# I2C-SPI_Communication.net
KiCad netlist of a schematic drawn in Altium Designer
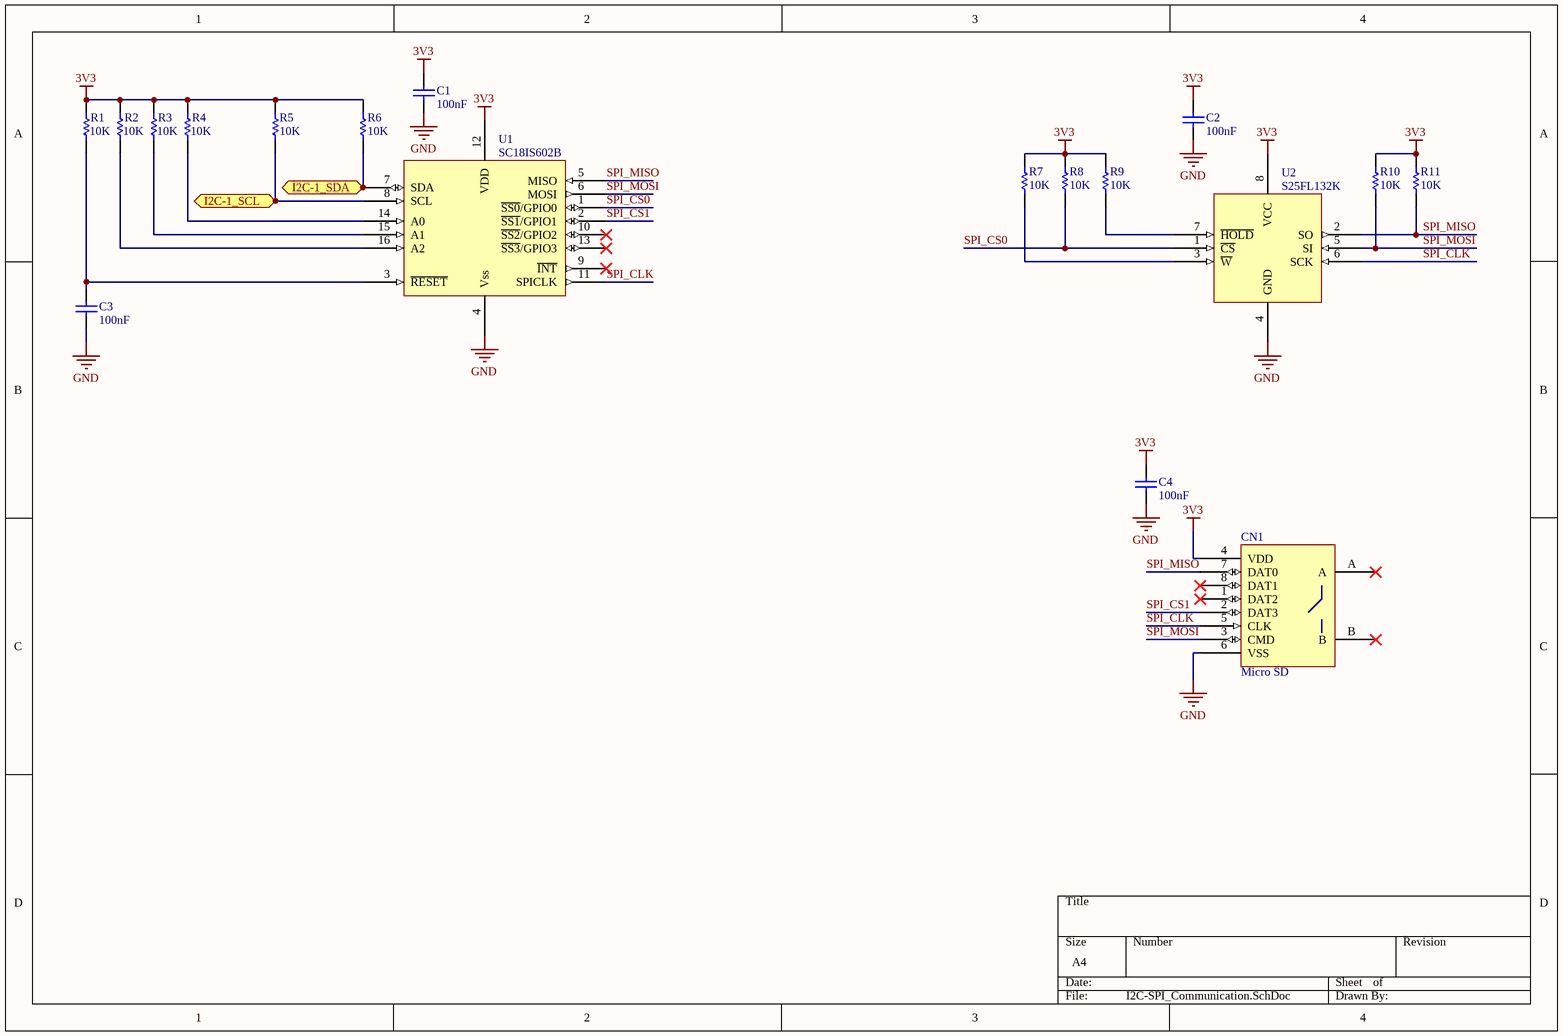
[diagram p0: I2C-SPI_Communication.SchDoc]

(export (version "E")
  (design (tool "Eeschema 10.0.6"))
  (components
    (comp (ref "C1")
      (value "100nF")
      (footprint "OBC_pcblib:CC1005-0402")
      (description "CAP CER 0.1UF 16V 10% X7R 0402")
      (fields
        (field (name "EVENDOR PART#") "490-3261-1-ND")
        (field (name "MANUFACTURER") "Murata Electronics North America")
      )
      (libsource (lib "OBC_schlib") (part "Capacitor"))
    )
    (comp (ref "C2")
      (value "100nF")
      (footprint "OBC_pcblib:CC1005-0402")
      (description "CAP CER 0.1UF 16V 10% X7R 0402")
      (fields
        (field (name "EVENDOR PART#") "490-3261-1-ND")
        (field (name "MANUFACTURER") "Murata Electronics North America")
      )
      (libsource (lib "OBC_schlib") (part "Capacitor"))
    )
    (comp (ref "C3")
      (value "100nF")
      (footprint "OBC_pcblib:CC1005-0402")
      (description "Capacitor")
      (libsource (lib "Schlib1") (part "Capacitor"))
    )
    (comp (ref "C4")
      (value "100nF")
      (footprint "OBC_pcblib:CC1005-0402")
      (description "CAP CER 0.1UF 16V 10% X7R 0402")
      (fields
        (field (name "EVENDOR PART#") "490-3261-1-ND")
        (field (name "MANUFACTURER") "Murata Electronics North America")
      )
      (libsource (lib "OBC_schlib") (part "Capacitor"))
    )
    (comp (ref "CN1")
      (value "Micro SD")
      (footprint "OBC_pcblib:MICROSD")
      (description "CONN MICRO SD R/A PUSH-PULL SMD")
      (fields
        (field (name "EVENDOR PART#") "HR1941CT-ND")
        (field (name "MANUFACTURER") "Hirose Electric Co Ltd")
      )
      (libsource (lib "Schlib1") (part "Micro SD"))
    )
    (comp (ref "R1")
      (value "10K")
      (footprint "AXIAL-0.3")
      (description "Resistor")
      (fields (field (name "Comment") "Res1") (field (name "PUBLISHER") "Altium Limited"))
      (libsource (lib "Miscellaneous Devices") (part "Res1"))
    )
    (comp (ref "R2")
      (value "10K")
      (footprint "AXIAL-0.3")
      (description "Resistor")
      (fields (field (name "Comment") "Res1") (field (name "PUBLISHER") "Altium Limited"))
      (libsource (lib "Miscellaneous Devices") (part "Res1"))
    )
    (comp (ref "R3")
      (value "10K")
      (footprint "AXIAL-0.3")
      (description "Resistor")
      (fields (field (name "Comment") "Res1") (field (name "PUBLISHER") "Altium Limited"))
      (libsource (lib "Miscellaneous Devices") (part "Res1"))
    )
    (comp (ref "R4")
      (value "10K")
      (footprint "AXIAL-0.3")
      (description "Resistor")
      (fields (field (name "Comment") "Res1") (field (name "PUBLISHER") "Altium Limited"))
      (libsource (lib "Miscellaneous Devices") (part "Res1"))
    )
    (comp (ref "R5")
      (value "10K")
      (footprint "OBC_pcblib:CR1005-0402_NP")
      (description "Resistor")
      (libsource (lib "Schlib1") (part "Resistor"))
    )
    (comp (ref "R6")
      (value "10K")
      (footprint "OBC_pcblib:CR1005-0402_NP")
      (description "Resistor")
      (libsource (lib "Schlib1") (part "Resistor"))
    )
    (comp (ref "R7")
      (value "10K")
      (footprint "OBC_pcblib:CR1005-0402")
      (description "RES SMD 10K OHM 1% 1/10W 0402")
      (fields
        (field (name "EVENDOR PART#") "P10.0KLCT-ND")
        (field (name "MANUFACTURER") "Panasonic Electronic Components")
      )
      (libsource (lib "OBC_schlib") (part "Resistor"))
    )
    (comp (ref "R8")
      (value "10K")
      (footprint "OBC_pcblib:CR1005-0402")
      (description "RES SMD 10K OHM 1% 1/10W 0402")
      (fields
        (field (name "EVENDOR PART#") "P10.0KLCT-ND")
        (field (name "MANUFACTURER") "Panasonic Electronic Components")
      )
      (libsource (lib "OBC_schlib") (part "Resistor"))
    )
    (comp (ref "R9")
      (value "10K")
      (footprint "OBC_pcblib:CR1005-0402")
      (description "RES SMD 10K OHM 1% 1/10W 0402")
      (fields
        (field (name "EVENDOR PART#") "P10.0KLCT-ND")
        (field (name "MANUFACTURER") "Panasonic Electronic Components")
      )
      (libsource (lib "OBC_schlib") (part "Resistor"))
    )
    (comp (ref "R10")
      (value "10K")
      (footprint "OBC_pcblib:CR1005-0402")
      (description "RES SMD 10K OHM 1% 1/10W 0402")
      (fields
        (field (name "EVENDOR PART#") "P10.0KLCT-ND")
        (field (name "MANUFACTURER") "Panasonic Electronic Components")
      )
      (libsource (lib "OBC_schlib") (part "Resistor"))
    )
    (comp (ref "R11")
      (value "10K")
      (footprint "OBC_pcblib:CR1005-0402")
      (description "RES SMD 10K OHM 1% 1/10W 0402")
      (fields
        (field (name "EVENDOR PART#") "P10.0KLCT-ND")
        (field (name "MANUFACTURER") "Panasonic Electronic Components")
      )
      (libsource (lib "OBC_schlib") (part "Resistor"))
    )
    (comp (ref "U1")
      (value "SC18IS602B")
      (footprint "TSSOP-16N")
      (description "IC BRIDGE I2C/SPI 16-TSSOP")
      (fields (field (name "EVENDORPART#") "568-10300-1-ND") (field (name "MANUFACTURER") "NXP USA Inc"))
      (libsource (lib "Schlib1") (part "SC18IS602B"))
    )
    (comp (ref "U2")
      (value "S25FL132K")
      (footprint "OBC_pcblib:SOIC-8N")
      (description "Flash 32Mb, 3V, 108Mhz CMOS SPI Flash")
      (fields (field (name "MANUFACTURER") "Spansion") (field (name "EVENDOR PART#") "797-25FL132K0XMFI041"))
      (libsource (lib "OBC_schlib") (part "S25FL132K"))
    )
  )
  (nets
    (net (code "1") (name "/I2C-1_SCL") (class "Default")
      (node (ref "R5") (pin "1") (pinfunction "1_1") (pintype "passive"))
      (node (ref "U1") (pin "8") (pinfunction "SCL_8") (pintype "input"))
    )
    (net (code "2") (name "/I2C-1_SDA") (class "Default")
      (node (ref "R6") (pin "1") (pinfunction "1_1") (pintype "passive"))
      (node (ref "U1") (pin "7") (pinfunction "SDA_7") (pintype "bidirectional"))
    )
    (net (code "3") (name "/SPI_CLK") (class "Default")
      (node (ref "CN1") (pin "5") (pinfunction "CLK_5") (pintype "input"))
      (node (ref "U1") (pin "11") (pinfunction "SPICLK_11") (pintype "output"))
      (node (ref "U2") (pin "6") (pinfunction "SCK_6") (pintype "input"))
    )
    (net (code "4") (name "/SPI_CS0") (class "Default")
      (node (ref "R8") (pin "1") (pinfunction "1_1") (pintype "passive"))
      (node (ref "U1") (pin "1") (pinfunction "~{SS0}/GPIO0_1") (pintype "bidirectional"))
      (node (ref "U2") (pin "1") (pinfunction "~{CS}_1") (pintype "input"))
    )
    (net (code "5") (name "/SPI_CS1") (class "Default")
      (node (ref "CN1") (pin "2") (pinfunction "DAT3_2") (pintype "bidirectional"))
      (node (ref "U1") (pin "2") (pinfunction "~{SS1}/GPIO1_2") (pintype "bidirectional"))
    )
    (net (code "6") (name "/SPI_MISO") (class "Default")
      (node (ref "CN1") (pin "7") (pinfunction "DAT0_7") (pintype "bidirectional"))
      (node (ref "R11") (pin "1") (pinfunction "1_1") (pintype "passive"))
      (node (ref "U1") (pin "5") (pinfunction "MISO_5") (pintype "input"))
      (node (ref "U2") (pin "2") (pinfunction "SO_2") (pintype "output"))
    )
    (net (code "7") (name "/SPI_MOSI") (class "Default")
      (node (ref "CN1") (pin "3") (pinfunction "CMD_3") (pintype "bidirectional"))
      (node (ref "R10") (pin "1") (pinfunction "1_1") (pintype "passive"))
      (node (ref "U1") (pin "6") (pinfunction "MOSI_6") (pintype "output"))
      (node (ref "U2") (pin "5") (pinfunction "SI_5") (pintype "input"))
    )
    (net (code "8") (name "3V3") (class "Default")
      (node (ref "C1") (pin "2") (pinfunction "2_2") (pintype "passive"))
      (node (ref "C2") (pin "2") (pinfunction "2_2") (pintype "passive"))
      (node (ref "C4") (pin "2") (pinfunction "2_2") (pintype "passive"))
      (node (ref "CN1") (pin "4") (pinfunction "VDD_4") (pintype "power_in"))
      (node (ref "R1") (pin "2") (pinfunction "2_2") (pintype "passive"))
      (node (ref "R10") (pin "2") (pinfunction "2_2") (pintype "passive"))
      (node (ref "R11") (pin "2") (pinfunction "2_2") (pintype "passive"))
      (node (ref "R2") (pin "2") (pinfunction "2_2") (pintype "passive"))
      (node (ref "R3") (pin "2") (pinfunction "2_2") (pintype "passive"))
      (node (ref "R4") (pin "2") (pinfunction "2_2") (pintype "passive"))
      (node (ref "R5") (pin "2") (pinfunction "2_2") (pintype "passive"))
      (node (ref "R6") (pin "2") (pinfunction "2_2") (pintype "passive"))
      (node (ref "R7") (pin "2") (pinfunction "2_2") (pintype "passive"))
      (node (ref "R8") (pin "2") (pinfunction "2_2") (pintype "passive"))
      (node (ref "R9") (pin "2") (pinfunction "2_2") (pintype "passive"))
      (node (ref "U1") (pin "12") (pinfunction "VDD_12") (pintype "power_in"))
      (node (ref "U2") (pin "8") (pinfunction "VCC_8") (pintype "power_in"))
    )
    (net (code "9") (name "GND") (class "Default")
      (node (ref "C1") (pin "1") (pinfunction "1_1") (pintype "passive"))
      (node (ref "C2") (pin "1") (pinfunction "1_1") (pintype "passive"))
      (node (ref "C3") (pin "1") (pinfunction "1_1") (pintype "passive"))
      (node (ref "C4") (pin "1") (pinfunction "1_1") (pintype "passive"))
      (node (ref "CN1") (pin "6") (pinfunction "VSS_6") (pintype "power_in"))
      (node (ref "U1") (pin "4") (pinfunction "Vss_4") (pintype "power_in"))
      (node (ref "U2") (pin "4") (pinfunction "GND_4") (pintype "power_in"))
    )
    (net (code "10") (name "Net-(U1-A0)") (class "Default")
      (node (ref "R4") (pin "1") (pinfunction "1_1") (pintype "passive"))
      (node (ref "U1") (pin "14") (pinfunction "A0_14") (pintype "input"))
    )
    (net (code "11") (name "Net-(U1-A1)") (class "Default")
      (node (ref "R3") (pin "1") (pinfunction "1_1") (pintype "passive"))
      (node (ref "U1") (pin "15") (pinfunction "A1_15") (pintype "input"))
    )
    (net (code "12") (name "Net-(U1-A2)") (class "Default")
      (node (ref "R2") (pin "1") (pinfunction "1_1") (pintype "passive"))
      (node (ref "U1") (pin "16") (pinfunction "A2_16") (pintype "input"))
    )
    (net (code "13") (name "Net-(U1-~{RESET})") (class "Default")
      (node (ref "C3") (pin "2") (pinfunction "2_2") (pintype "passive"))
      (node (ref "R1") (pin "1") (pinfunction "1_1") (pintype "passive"))
      (node (ref "U1") (pin "3") (pinfunction "~{RESET}_3") (pintype "input"))
    )
    (net (code "14") (name "Net-(U2-~{HOLD})") (class "Default")
      (node (ref "R9") (pin "1") (pinfunction "1_1") (pintype "passive"))
      (node (ref "U2") (pin "7") (pinfunction "~{HOLD}_7") (pintype "input"))
    )
    (net (code "15") (name "Net-(U2-~{W})") (class "Default")
      (node (ref "R7") (pin "1") (pinfunction "1_1") (pintype "passive"))
      (node (ref "U2") (pin "3") (pinfunction "~{W}_3") (pintype "input"))
    )
    (net (code "16") (name "unconnected-(CN1-DAT1-Pad8)") (class "Default")
      (node (ref "CN1") (pin "8") (pinfunction "DAT1_8") (pintype "bidirectional+no_connect"))
    )
    (net (code "17") (name "unconnected-(CN1-DAT2-Pad1)") (class "Default")
      (node (ref "CN1") (pin "1") (pinfunction "DAT2_1") (pintype "bidirectional+no_connect"))
    )
    (net (code "18") (name "unconnected-(CN1-PadA)") (class "Default")
      (node (ref "CN1") (pin "A") (pinfunction "A_A") (pintype "passive+no_connect"))
    )
    (net (code "19") (name "unconnected-(CN1-PadB)") (class "Default")
      (node (ref "CN1") (pin "B") (pinfunction "B_B") (pintype "passive+no_connect"))
    )
    (net (code "20") (name "unconnected-(U1-~{INT}-Pad9)") (class "Default")
      (node (ref "U1") (pin "9") (pinfunction "~{INT}_9") (pintype "output+no_connect"))
    )
    (net (code "21") (name "unconnected-(U1-~{SS2}{slash}GPIO2-Pad10)") (class "Default")
      (node (ref "U1") (pin "10") (pinfunction "~{SS2}/GPIO2_10") (pintype "bidirectional+no_connect"))
    )
    (net (code "22") (name "unconnected-(U1-~{SS3}{slash}GPIO3-Pad13)") (class "Default")
      (node (ref "U1") (pin "13") (pinfunction "~{SS3}/GPIO3_13") (pintype "bidirectional+no_connect"))
    )
  )
)
